# ISO_I2C_ISO1540DR.net
KiCad netlist of a schematic drawn in Altium Designer
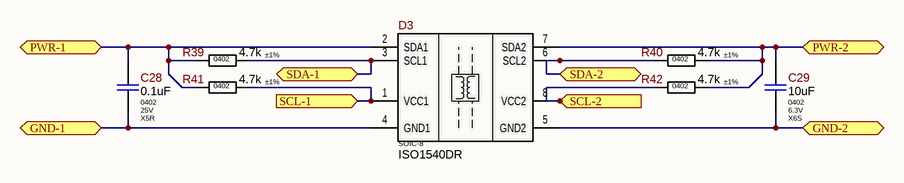
[diagram p0: ISO_I2C_ISO1540DR.SchDoc]

(export (version "E")
  (design (tool "Eeschema 10.0.6"))
  (components
    (comp (ref "C28")
      (value "0.1uF")
      (footprint "C_CERAMIC_0402_MED")
      (description "100nF 25V X5R ±10% 0402 Ceramic Capacitor RoHS")
      (fields
        (field (name "PACKAGE") "0402")
        (field (name "VOLTAGE") "25V")
        (field (name "DIELECTRIC TYPE") "X5R")
        (field (name "PART NUMBER") "CL05A104KA5NNNC")
        (field (name "MANUFACTURER") "Samsung Electro-Mechanics")
      )
      (libsource (lib "EL.XXX.T01") (part "Capacitor-NonPolar"))
    )
    (comp (ref "C29")
      (value "10uF")
      (footprint "C_CERAMIC_0402_MED")
      (description "10uF 6.3V X6S ±20% 0402 Ceramic Capacitor RoHS")
      (fields
        (field (name "PACKAGE") "0402")
        (field (name "VOLTAGE") "6.3V")
        (field (name "DIELECTRIC TYPE") "X6S")
        (field (name "PART NUMBER") "GRM155C80J106ME11D")
        (field (name "MANUFACTURER") "Murata Electronics")
      )
      (libsource (lib "EL.XXX.T01") (part "Capacitor-NonPolar"))
    )
    (comp (ref "D3")
      (value "ISO1540DR")
      (footprint "SOIC-8_W3.9MM")
      (description "I2C Digital Isolator 2500Vrms 2 Channel 1Mbps 25kV/us, SOIC-8")
      (fields
        (field (name "PACKAGE") "SOIC-8")
        (field (name "PART NUMBER") "ISO1540DR")
        (field (name "MANUFACTURER") "Texas Instruments")
      )
      (libsource (lib "EL.XXX.T01") (part "ISO1540DR"))
    )
    (comp (ref "R39")
      (value "4.7k")
      (footprint "R_ANY_CHIP_0402_MED")
      (description "4.7 kOhms ±1% 1/16W 0402 Thick Film Resistor")
      (fields
        (field (name "TOLERANCE") "±1%")
        (field (name "PACKAGE") "0402")
        (field (name "PART NUMBER") "RC0402FR-074K7L")
        (field (name "MANUFACTURER") "Yageo")
      )
      (libsource (lib "EL.XXX.T01") (part "Resistor"))
    )
    (comp (ref "R40")
      (value "4.7k")
      (footprint "R_ANY_CHIP_0402_MED")
      (description "4.7 kOhms ±1% 1/16W 0402 Thick Film Resistor")
      (fields
        (field (name "TOLERANCE") "±1%")
        (field (name "PACKAGE") "0402")
        (field (name "PART NUMBER") "RC0402FR-074K7L")
        (field (name "MANUFACTURER") "Yageo")
      )
      (libsource (lib "EL.XXX.T01") (part "Resistor"))
    )
    (comp (ref "R41")
      (value "4.7k")
      (footprint "R_ANY_CHIP_0402_MED")
      (description "4.7 kOhms ±1% 1/16W 0402 Thick Film Resistor")
      (fields
        (field (name "TOLERANCE") "±1%")
        (field (name "PACKAGE") "0402")
        (field (name "PART NUMBER") "RC0402FR-074K7L")
        (field (name "MANUFACTURER") "Yageo")
      )
      (libsource (lib "EL.XXX.T01") (part "Resistor"))
    )
    (comp (ref "R42")
      (value "4.7k")
      (footprint "R_ANY_CHIP_0402_MED")
      (description "4.7 kOhms ±1% 1/16W 0402 Thick Film Resistor")
      (fields
        (field (name "TOLERANCE") "±1%")
        (field (name "PACKAGE") "0402")
        (field (name "PART NUMBER") "RC0402FR-074K7L")
        (field (name "MANUFACTURER") "Yageo")
      )
      (libsource (lib "EL.XXX.T01") (part "Resistor"))
    )
  )
  (nets
    (net (code "1") (name "/GND-1") (class "Default")
      (node (ref "C28") (pin "2") (pinfunction "2_2") (pintype "passive"))
      (node (ref "D3") (pin "4") (pinfunction "GND1_4") (pintype "passive"))
    )
    (net (code "2") (name "/GND-2") (class "Default")
      (node (ref "C29") (pin "2") (pinfunction "2_2") (pintype "passive"))
      (node (ref "D3") (pin "5") (pinfunction "GND2_5") (pintype "passive"))
    )
    (net (code "3") (name "/PWR-1") (class "Default")
      (node (ref "C28") (pin "1") (pinfunction "1_1") (pintype "passive"))
      (node (ref "D3") (pin "2") (pinfunction "SDA1_2") (pintype "passive"))
      (node (ref "R39") (pin "1") (pintype "passive"))
      (node (ref "R41") (pin "1") (pintype "passive"))
    )
    (net (code "4") (name "/PWR-2") (class "Default")
      (node (ref "C29") (pin "1") (pinfunction "1_1") (pintype "passive"))
      (node (ref "D3") (pin "7") (pinfunction "SDA2_7") (pintype "passive"))
      (node (ref "R40") (pin "2") (pintype "passive"))
      (node (ref "R42") (pin "2") (pintype "passive"))
    )
    (net (code "5") (name "/SCL-1") (class "Default")
      (node (ref "D3") (pin "1") (pinfunction "VCC1_1") (pintype "passive"))
      (node (ref "R41") (pin "2") (pintype "passive"))
    )
    (net (code "6") (name "/SCL-2") (class "Default")
      (node (ref "D3") (pin "8") (pinfunction "VCC2_8") (pintype "passive"))
      (node (ref "R42") (pin "1") (pintype "passive"))
    )
    (net (code "7") (name "/SDA-1") (class "Default")
      (node (ref "D3") (pin "3") (pinfunction "SCL1_3") (pintype "passive"))
      (node (ref "R39") (pin "2") (pintype "passive"))
    )
    (net (code "8") (name "/SDA-2") (class "Default")
      (node (ref "D3") (pin "6") (pinfunction "SCL2_6") (pintype "passive"))
      (node (ref "R40") (pin "1") (pintype "passive"))
    )
  )
)
